# Connectors.net
KiCad netlist of a schematic drawn in Altium Designer
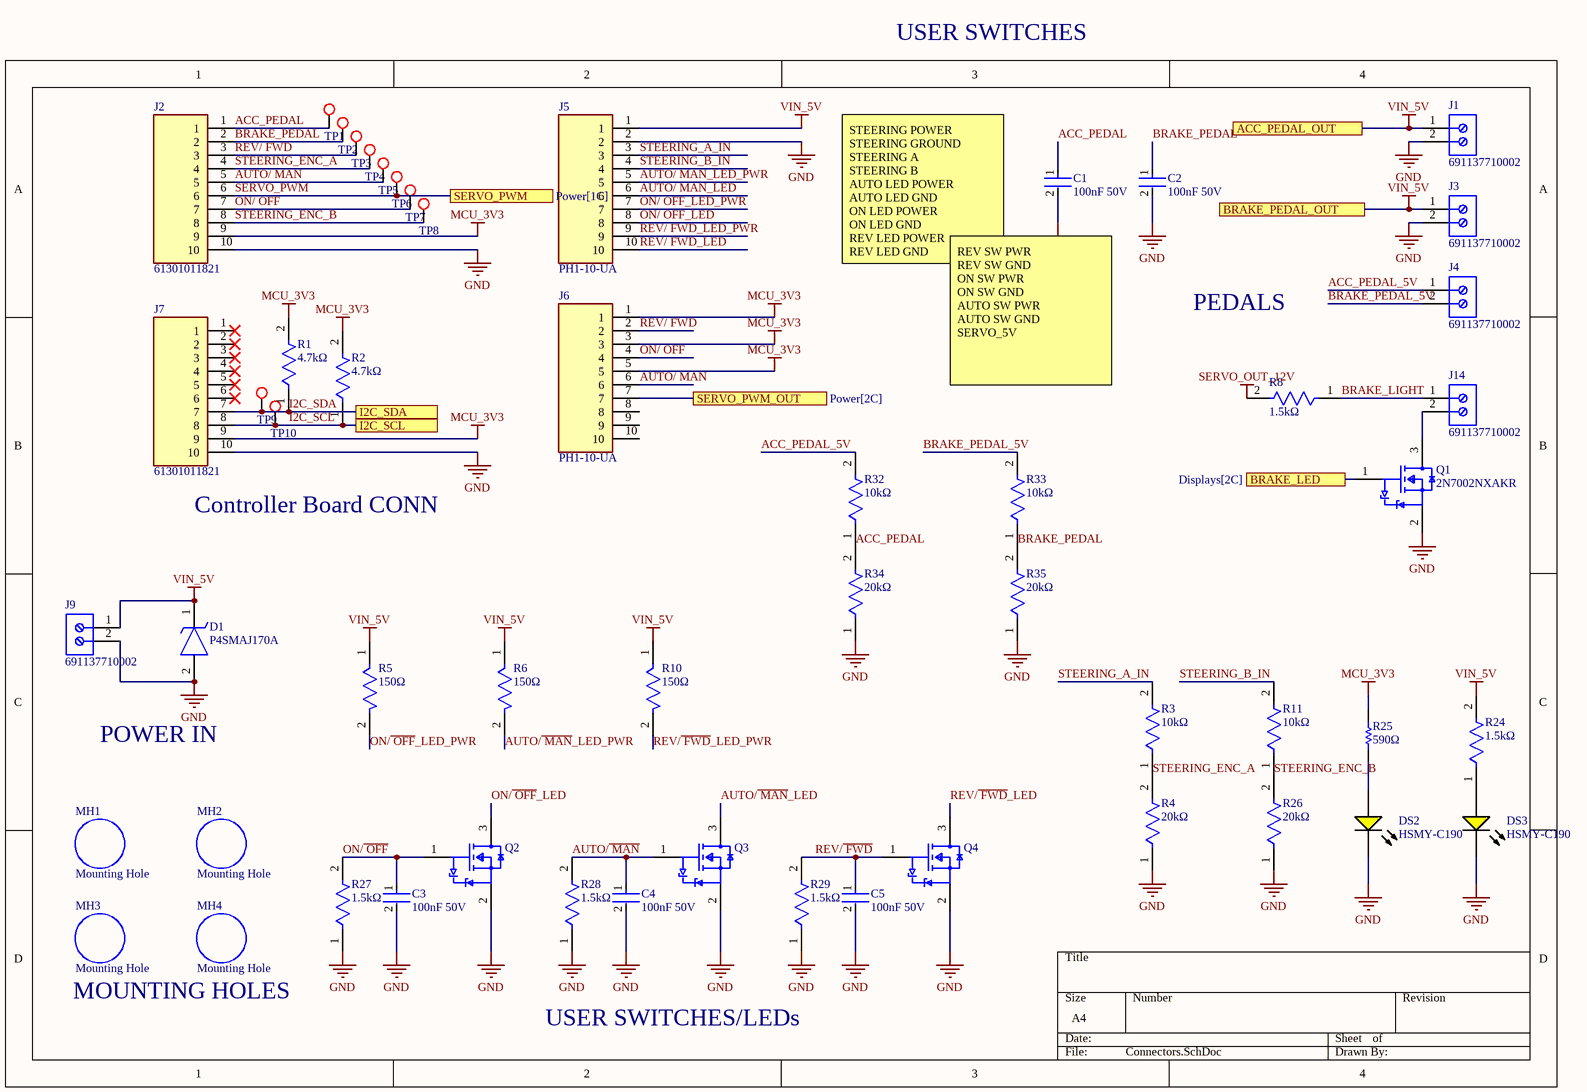
[diagram p0: Connectors.SchDoc]

(export (version "E")
  (design (tool "Eeschema 10.0.6"))
  (components
    (comp (ref "C1")
      (value "100nF 50V")
      (footprint "FP-CL31-IPC_C")
      (description "Cap Ceramic 100nF 50V X7R ±10% SMD 1206 +125°C Embossed T/R")
      (fields (field (name "TOLERANCE") "10%"))
      (libsource (lib "Altium Content Vault") (part "b4654b650e69147ec39a6b967a45e02"))
    )
    (comp (ref "C2")
      (value "100nF 50V")
      (footprint "FP-CL31-IPC_C")
      (description "Cap Ceramic 100nF 50V X7R ±10% SMD 1206 +125°C Embossed T/R")
      (fields (field (name "TOLERANCE") "10%"))
      (libsource (lib "Altium Content Vault") (part "b4654b650e69147ec39a6b967a45e02"))
    )
    (comp (ref "C3")
      (value "100nF 50V")
      (footprint "FP-CL31-IPC_C")
      (description "Cap Ceramic 100nF 50V X7R ±10% SMD 1206 +125°C Embossed T/R")
      (fields (field (name "TOLERANCE") "10%"))
      (libsource (lib "Altium Content Vault") (part "b4654b650e69147ec39a6b967a45e02"))
    )
    (comp (ref "C4")
      (value "100nF 50V")
      (footprint "FP-CL31-IPC_C")
      (description "Cap Ceramic 100nF 50V X7R ±10% SMD 1206 +125°C Embossed T/R")
      (fields (field (name "TOLERANCE") "10%"))
      (libsource (lib "Altium Content Vault") (part "b4654b650e69147ec39a6b967a45e02"))
    )
    (comp (ref "C5")
      (value "100nF 50V")
      (footprint "FP-CL31-IPC_C")
      (description "Cap Ceramic 100nF 50V X7R ±10% SMD 1206 +125°C Embossed T/R")
      (fields (field (name "TOLERANCE") "10%"))
      (libsource (lib "Altium Content Vault") (part "b4654b650e69147ec39a6b967a45e02"))
    )
    (comp (ref "D1")
      (value "P4SMAJ170A")
      (footprint "SamacSys:DIOM5027X240N")
      (description "TVS Diode (Uni-directional)")
      (libsource (lib "*") (part "P4SMAJ170A"))
    )
    (comp (ref "DS2")
      (value "HSMY-C190")
      (footprint "AVAG-HSMX-C190_V")
      (description "LED Uni-Color Yellow, 65 mW, 20 mA, -40 to 85 degC, 2-Pin SMD, RoHS, Tape and Reel")
      (fields (field (name "TOLERANCE") "1%"))
      (libsource (lib "Altium Content Vault") (part "LED-YELLOW-AK-2"))
    )
    (comp (ref "DS3")
      (value "HSMY-C190")
      (footprint "AVAG-HSMX-C190_V")
      (description "LED Uni-Color Yellow, 65 mW, 20 mA, -40 to 85 degC, 2-Pin SMD, RoHS, Tape and Reel")
      (fields (field (name "TOLERANCE") "1%"))
      (libsource (lib "Altium Content Vault") (part "LED-YELLOW-AK-2"))
    )
    (comp (ref "J1")
      (value "691137710002")
      (footprint "691137710002")
      (libsource (lib "Altium Content Vault") (part "TBL - 1R - 02P - Screw"))
    )
    (comp (ref "J2")
      (value "61301011821")
      (footprint "SamacSys:RHDR10W60P0X254_1X10_2590X250X850P")
      (description "Connector")
      (fields (field (name "MOUSER PART NUMBER") "710-61301011821"))
      (libsource (lib "*") (part "61301011821"))
    )
    (comp (ref "J3")
      (value "691137710002")
      (footprint "691137710002")
      (libsource (lib "Altium Content Vault") (part "TBL - 1R - 02P - Screw"))
    )
    (comp (ref "J4")
      (value "691137710002")
      (footprint "691137710002")
      (libsource (lib "Altium Content Vault") (part "TBL - 1R - 02P - Screw"))
    )
    (comp (ref "J5")
      (value "PH1-10-UA")
      (footprint "SamacSys:HDRV10W64P0X254_1X10_2540X249X886P")
      (description "Connector")
      (fields (field (name "MOUSER PART NUMBER") "737-PH1-10-UA"))
      (libsource (lib "*") (part "PH1-10-UA"))
    )
    (comp (ref "J6")
      (value "PH1-10-UA")
      (footprint "SamacSys:HDRV10W64P0X254_1X10_2540X249X886P")
      (description "Connector")
      (fields (field (name "MOUSER PART NUMBER") "737-PH1-10-UA"))
      (libsource (lib "*") (part "PH1-10-UA"))
    )
    (comp (ref "J7")
      (value "61301011821")
      (footprint "SamacSys:RHDR10W60P0X254_1X10_2590X250X850P")
      (description "Connector")
      (fields (field (name "MOUSER PART NUMBER") "710-61301011821"))
      (libsource (lib "*") (part "61301011821"))
    )
    (comp (ref "J9")
      (value "691137710002")
      (footprint "691137710002")
      (libsource (lib "Altium Content Vault") (part "TBL - 1R - 02P - Screw"))
    )
    (comp (ref "J14")
      (value "691137710002")
      (footprint "691137710002")
      (libsource (lib "Altium Content Vault") (part "TBL - 1R - 02P - Screw"))
    )
    (comp (ref "MH1")
      (value "Mounting Hole")
      (footprint "Mounting Hole")
      (libsource (lib "Schlib1") (part "Mounting Hole"))
    )
    (comp (ref "MH2")
      (value "Mounting Hole")
      (footprint "Mounting Hole")
      (libsource (lib "Schlib1") (part "Mounting Hole"))
    )
    (comp (ref "MH3")
      (value "Mounting Hole")
      (footprint "Mounting Hole")
      (libsource (lib "Schlib1") (part "Mounting Hole"))
    )
    (comp (ref "MH4")
      (value "Mounting Hole")
      (footprint "Mounting Hole")
      (libsource (lib "Schlib1") (part "Mounting Hole"))
    )
    (comp (ref "Q1")
      (value "2N7002NXAKR")
      (footprint "FP-SOT23-IPC_B")
      (description "2N7002NXAK/SOT23/TO-236AB")
      (libsource (lib "Altium Content Vault") (part "bf18956dcdab3ff4da62eb44f668dfe"))
    )
    (comp (ref "Q2")
      (value "2N7002NXAKR")
      (footprint "FP-SOT23-IPC_B")
      (description "2N7002NXAK/SOT23/TO-236AB")
      (libsource (lib "Altium Content Vault") (part "bf18956dcdab3ff4da62eb44f668dfe"))
    )
    (comp (ref "Q3")
      (value "2N7002NXAKR")
      (footprint "FP-SOT23-IPC_B")
      (description "2N7002NXAK/SOT23/TO-236AB")
      (libsource (lib "Altium Content Vault") (part "bf18956dcdab3ff4da62eb44f668dfe"))
    )
    (comp (ref "Q4")
      (value "2N7002NXAKR")
      (footprint "FP-SOT23-IPC_B")
      (description "2N7002NXAK/SOT23/TO-236AB")
      (libsource (lib "Altium Content Vault") (part "bf18956dcdab3ff4da62eb44f668dfe"))
    )
    (comp (ref "R1")
      (value "4.7kΩ")
      (footprint "FP-RT0805-MFG")
      (description "RES SMD 4.7K OHM 1% 1/8W 0805")
      (fields (field (name "TOLERANCE") "0.0001") (field (name "MANUFACTURER PART NUMBER") "RT0805FRE074K7L"))
      (libsource (lib "Altium Content Vault") (part "1029c3af85768c4190bb7ad29bc67b5"))
    )
    (comp (ref "R2")
      (value "4.7kΩ")
      (footprint "FP-RT0805-MFG")
      (description "RES SMD 4.7K OHM 1% 1/8W 0805")
      (fields (field (name "TOLERANCE") "0.0001") (field (name "MANUFACTURER PART NUMBER") "RT0805FRE074K7L"))
      (libsource (lib "Altium Content Vault") (part "1029c3af85768c4190bb7ad29bc67b5"))
    )
    (comp (ref "R3")
      (value "10kΩ")
      (footprint "FP-RT0603-MFG")
      (description "RES SMD 10K OHM 0.1% 1/10W 0603")
      (fields
        (field (name "TOLERANCE") "0.001")
        (field (name "OCTOPART") "https://octopart.com/rt0603bre0710kl-yageo-1273959")
      )
      (libsource (lib "Altium Content Vault") (part "1029c3af85768c4190bb7ad29bc67b5"))
    )
    (comp (ref "R4")
      (value "20kΩ")
      (footprint "FP-RT0805-MFG")
      (description "RES SMD 20K OHM 1% 1/8W 0805")
      (fields
        (field (name "MANUFACTURER") "Yageo")
        (field (name "MANUFACTURER PART NUMBER") "RT0805FRE0720KL")
      )
      (libsource (lib "Altium Content Vault") (part "1029c3af85768c4190bb7ad29bc67b5"))
    )
    (comp (ref "R5")
      (value "150Ω")
      (footprint "FP-RT0603-MFG")
      (description "RES SMD 150 OHM 1% 1/10W 0603")
      (fields
        (field (name "OCTOPART") "https://octopart.com/rt0603fre07150rl-yageo-39804552")
        (field (name "MANUFACTURER PART NUMBER") "RT0603FRE07150RL")
      )
      (libsource (lib "Altium Content Vault") (part "1029c3af85768c4190bb7ad29bc67b5"))
    )
    (comp (ref "R6")
      (value "150Ω")
      (footprint "FP-RT0603-MFG")
      (description "RES SMD 150 OHM 1% 1/10W 0603")
      (fields
        (field (name "OCTOPART") "https://octopart.com/rt0603fre07150rl-yageo-39804552")
        (field (name "MANUFACTURER PART NUMBER") "RT0603FRE07150RL")
      )
      (libsource (lib "Altium Content Vault") (part "1029c3af85768c4190bb7ad29bc67b5"))
    )
    (comp (ref "R8")
      (value "1.5kΩ")
      (footprint "FP-CRCW0603-e3-IPC_A")
      (description "RES Thick Film, 1.5kΩ, 1%, 0.1W, 100ppm/°C, 0603")
      (fields (field (name "TOLERANCE") "1%"))
      (libsource (lib "Altium Content Vault") (part "1029c3af85768c4190bb7ad29bc67b5"))
    )
    (comp (ref "R10")
      (value "150Ω")
      (footprint "FP-RT0603-MFG")
      (description "RES SMD 150 OHM 1% 1/10W 0603")
      (fields
        (field (name "OCTOPART") "https://octopart.com/rt0603fre07150rl-yageo-39804552")
        (field (name "MANUFACTURER PART NUMBER") "RT0603FRE07150RL")
      )
      (libsource (lib "Altium Content Vault") (part "1029c3af85768c4190bb7ad29bc67b5"))
    )
    (comp (ref "R11")
      (value "10kΩ")
      (footprint "FP-RT0603-MFG")
      (description "RES SMD 10K OHM 0.1% 1/10W 0603")
      (fields
        (field (name "TOLERANCE") "0.001")
        (field (name "OCTOPART") "https://octopart.com/rt0603bre0710kl-yageo-1273959")
      )
      (libsource (lib "Altium Content Vault") (part "1029c3af85768c4190bb7ad29bc67b5"))
    )
    (comp (ref "R24")
      (value "1.5kΩ")
      (footprint "FP-RC1608-IPC_B")
      (description "Res Thick Film 0603 1.5kΩ 1% 0.1W ±100ppm/°C Molded SMD T/R")
      (fields (field (name "TOLERANCE") "1%"))
      (libsource (lib "Altium Content Vault") (part "1029c3af85768c4190bb7ad29bc67b5"))
    )
    (comp (ref "R25")
      (value "590Ω")
      (footprint "RESC1608X55X25ML10T15")
      (fields (field (name "PART NUMBER") "RC0603FR-07590RL") (field (name "MANUFACTURER") "Yageo"))
      (libsource (lib "Altium Content Vault") (part "RES"))
    )
    (comp (ref "R26")
      (value "20kΩ")
      (footprint "FP-RT0805-MFG")
      (description "RES SMD 20K OHM 1% 1/8W 0805")
      (fields
        (field (name "MANUFACTURER") "Yageo")
        (field (name "MANUFACTURER PART NUMBER") "RT0805FRE0720KL")
      )
      (libsource (lib "Altium Content Vault") (part "1029c3af85768c4190bb7ad29bc67b5"))
    )
    (comp (ref "R27")
      (value "1.5kΩ")
      (footprint "FP-CRCW0603-e3-IPC_A")
      (description "RES Thick Film, 1.5kΩ, 1%, 0.1W, 100ppm/°C, 0603")
      (fields (field (name "TOLERANCE") "1%"))
      (libsource (lib "Altium Content Vault") (part "1029c3af85768c4190bb7ad29bc67b5"))
    )
    (comp (ref "R28")
      (value "1.5kΩ")
      (footprint "FP-CRCW0603-e3-IPC_A")
      (description "RES Thick Film, 1.5kΩ, 1%, 0.1W, 100ppm/°C, 0603")
      (fields (field (name "TOLERANCE") "1%"))
      (libsource (lib "Altium Content Vault") (part "1029c3af85768c4190bb7ad29bc67b5"))
    )
    (comp (ref "R29")
      (value "1.5kΩ")
      (footprint "FP-CRCW0603-e3-IPC_A")
      (description "RES Thick Film, 1.5kΩ, 1%, 0.1W, 100ppm/°C, 0603")
      (fields (field (name "TOLERANCE") "1%"))
      (libsource (lib "Altium Content Vault") (part "1029c3af85768c4190bb7ad29bc67b5"))
    )
    (comp (ref "R32")
      (value "10kΩ")
      (footprint "FP-RT0603-MFG")
      (description "RES SMD 10K OHM 0.1% 1/10W 0603")
      (fields
        (field (name "TOLERANCE") "0.001")
        (field (name "OCTOPART") "https://octopart.com/rt0603bre0710kl-yageo-1273959")
      )
      (libsource (lib "Altium Content Vault") (part "1029c3af85768c4190bb7ad29bc67b5"))
    )
    (comp (ref "R33")
      (value "10kΩ")
      (footprint "FP-RT0603-MFG")
      (description "RES SMD 10K OHM 0.1% 1/10W 0603")
      (fields
        (field (name "TOLERANCE") "0.001")
        (field (name "OCTOPART") "https://octopart.com/rt0603bre0710kl-yageo-1273959")
      )
      (libsource (lib "Altium Content Vault") (part "1029c3af85768c4190bb7ad29bc67b5"))
    )
    (comp (ref "R34")
      (value "20kΩ")
      (footprint "FP-RT0805-MFG")
      (description "RES SMD 20K OHM 1% 1/8W 0805")
      (fields
        (field (name "MANUFACTURER") "Yageo")
        (field (name "MANUFACTURER PART NUMBER") "RT0805FRE0720KL")
      )
      (libsource (lib "Altium Content Vault") (part "1029c3af85768c4190bb7ad29bc67b5"))
    )
    (comp (ref "R35")
      (value "20kΩ")
      (footprint "FP-RT0805-MFG")
      (description "RES SMD 20K OHM 1% 1/8W 0805")
      (fields
        (field (name "MANUFACTURER") "Yageo")
        (field (name "MANUFACTURER PART NUMBER") "RT0805FRE0720KL")
      )
      (libsource (lib "Altium Content Vault") (part "1029c3af85768c4190bb7ad29bc67b5"))
    )
    (comp (ref "TP1") (value "TP") (footprint "Testpoint") (libsource (lib "Schlib1") (part "Testpoint")))
    (comp (ref "TP2") (value "TP") (footprint "Testpoint") (libsource (lib "Schlib1") (part "Testpoint")))
    (comp (ref "TP3") (value "TP") (footprint "Testpoint") (libsource (lib "Schlib1") (part "Testpoint")))
    (comp (ref "TP4") (value "TP") (footprint "Testpoint") (libsource (lib "Schlib1") (part "Testpoint")))
    (comp (ref "TP5") (value "TP") (footprint "Testpoint") (libsource (lib "Schlib1") (part "Testpoint")))
    (comp (ref "TP6") (value "TP") (footprint "Testpoint") (libsource (lib "Schlib1") (part "Testpoint")))
    (comp (ref "TP7") (value "TP") (footprint "Testpoint") (libsource (lib "Schlib1") (part "Testpoint")))
    (comp (ref "TP8") (value "TP") (footprint "Testpoint") (libsource (lib "Schlib1") (part "Testpoint")))
    (comp (ref "TP9") (value "TP") (footprint "Testpoint") (libsource (lib "Schlib1") (part "Testpoint")))
    (comp (ref "TP10") (value "TP") (footprint "Testpoint") (libsource (lib "Schlib1") (part "Testpoint")))
  )
  (nets
    (net (code "1") (name "/ACC_PEDAL") (class "Default")
      (node (ref "C1") (pin "1") (pinfunction "1_1") (pintype "passive"))
      (node (ref "J2") (pin "1") (pinfunction "1_1") (pintype "passive"))
      (node (ref "R32") (pin "1") (pinfunction "1_1") (pintype "passive"))
      (node (ref "R34") (pin "2") (pinfunction "2_2") (pintype "passive"))
      (node (ref "TP1") (pin "0") (pinfunction "0_0") (pintype "passive"))
    )
    (net (code "2") (name "/ACC_PEDAL_5V") (class "Default")
      (node (ref "J4") (pin "1") (pinfunction "1_1") (pintype "passive"))
      (node (ref "R32") (pin "2") (pinfunction "2_2") (pintype "passive"))
    )
    (net (code "3") (name "/AUTO{slash}~{ MAN}") (class "Default")
      (node (ref "C4") (pin "1") (pinfunction "1_1") (pintype "passive"))
      (node (ref "J2") (pin "5") (pinfunction "5_5") (pintype "passive"))
      (node (ref "J6") (pin "6") (pinfunction "6_6") (pintype "passive"))
      (node (ref "Q3") (pin "1") (pinfunction "G_1") (pintype "passive"))
      (node (ref "R28") (pin "2") (pinfunction "2_2") (pintype "passive"))
      (node (ref "TP5") (pin "0") (pinfunction "0_0") (pintype "passive"))
    )
    (net (code "4") (name "/AUTO{slash}~{ MAN}_LED") (class "Default")
      (node (ref "J5") (pin "6") (pinfunction "6_6") (pintype "passive"))
      (node (ref "Q3") (pin "3") (pinfunction "D_3") (pintype "passive"))
    )
    (net (code "5") (name "/AUTO{slash}~{ MAN}_LED_PWR") (class "Default")
      (node (ref "J5") (pin "5") (pinfunction "5_5") (pintype "passive"))
      (node (ref "R6") (pin "2") (pinfunction "2_2") (pintype "passive"))
    )
    (net (code "6") (name "/BRAKE_LED") (class "Default")
      (node (ref "Q1") (pin "1") (pinfunction "G_1") (pintype "passive"))
    )
    (net (code "7") (name "/BRAKE_LIGHT") (class "Default")
      (node (ref "J14") (pin "1") (pinfunction "1_1") (pintype "passive"))
      (node (ref "R8") (pin "1") (pinfunction "1_1") (pintype "passive"))
    )
    (net (code "8") (name "/BRAKE_PEDAL") (class "Default")
      (node (ref "C2") (pin "1") (pinfunction "1_1") (pintype "passive"))
      (node (ref "J2") (pin "2") (pinfunction "2_2") (pintype "passive"))
      (node (ref "R33") (pin "1") (pinfunction "1_1") (pintype "passive"))
      (node (ref "R35") (pin "2") (pinfunction "2_2") (pintype "passive"))
      (node (ref "TP2") (pin "0") (pinfunction "0_0") (pintype "passive"))
    )
    (net (code "9") (name "/BRAKE_PEDAL_5V") (class "Default")
      (node (ref "J4") (pin "2") (pinfunction "2_2") (pintype "passive"))
      (node (ref "R33") (pin "2") (pinfunction "2_2") (pintype "passive"))
    )
    (net (code "10") (name "/I2C_SCL") (class "Default")
      (node (ref "J7") (pin "8") (pinfunction "8_8") (pintype "passive"))
      (node (ref "R2") (pin "1") (pinfunction "1_1") (pintype "passive"))
      (node (ref "TP10") (pin "0") (pinfunction "0_0") (pintype "passive"))
    )
    (net (code "11") (name "/I2C_SDA") (class "Default")
      (node (ref "J7") (pin "7") (pinfunction "7_7") (pintype "passive"))
      (node (ref "R1") (pin "1") (pinfunction "1_1") (pintype "passive"))
      (node (ref "TP9") (pin "0") (pinfunction "0_0") (pintype "passive"))
    )
    (net (code "12") (name "/ON{slash}~{ OFF}") (class "Default")
      (node (ref "C3") (pin "1") (pinfunction "1_1") (pintype "passive"))
      (node (ref "J2") (pin "7") (pinfunction "7_7") (pintype "passive"))
      (node (ref "J6") (pin "4") (pinfunction "4_4") (pintype "passive"))
      (node (ref "Q2") (pin "1") (pinfunction "G_1") (pintype "passive"))
      (node (ref "R27") (pin "2") (pinfunction "2_2") (pintype "passive"))
      (node (ref "TP7") (pin "0") (pinfunction "0_0") (pintype "passive"))
    )
    (net (code "13") (name "/ON{slash}~{ OFF}_LED") (class "Default")
      (node (ref "J5") (pin "8") (pinfunction "8_8") (pintype "passive"))
      (node (ref "Q2") (pin "3") (pinfunction "D_3") (pintype "passive"))
    )
    (net (code "14") (name "/ON{slash}~{ OFF}_LED_PWR") (class "Default")
      (node (ref "J5") (pin "7") (pinfunction "7_7") (pintype "passive"))
      (node (ref "R5") (pin "2") (pinfunction "2_2") (pintype "passive"))
    )
    (net (code "15") (name "/REV{slash}~{ FWD}") (class "Default")
      (node (ref "C5") (pin "1") (pinfunction "1_1") (pintype "passive"))
      (node (ref "J2") (pin "3") (pinfunction "3_3") (pintype "passive"))
      (node (ref "J6") (pin "2") (pinfunction "2_2") (pintype "passive"))
      (node (ref "Q4") (pin "1") (pinfunction "G_1") (pintype "passive"))
      (node (ref "R29") (pin "2") (pinfunction "2_2") (pintype "passive"))
      (node (ref "TP3") (pin "0") (pinfunction "0_0") (pintype "passive"))
    )
    (net (code "16") (name "/REV{slash}~{ FWD}_LED") (class "Default")
      (node (ref "J5") (pin "10") (pinfunction "10_10") (pintype "passive"))
      (node (ref "Q4") (pin "3") (pinfunction "D_3") (pintype "passive"))
    )
    (net (code "17") (name "/REV{slash}~{ FWD}_LED_PWR") (class "Default")
      (node (ref "J5") (pin "9") (pinfunction "9_9") (pintype "passive"))
      (node (ref "R10") (pin "2") (pinfunction "2_2") (pintype "passive"))
    )
    (net (code "18") (name "/SERVO_PWM") (class "Default")
      (node (ref "J2") (pin "6") (pinfunction "6_6") (pintype "passive"))
      (node (ref "TP6") (pin "0") (pinfunction "0_0") (pintype "passive"))
    )
    (net (code "19") (name "/SERVO_PWM_OUT") (class "Default")
      (node (ref "J6") (pin "7") (pinfunction "7_7") (pintype "passive"))
    )
    (net (code "20") (name "/STEERING_A_IN") (class "Default")
      (node (ref "J5") (pin "3") (pinfunction "3_3") (pintype "passive"))
      (node (ref "R3") (pin "2") (pinfunction "2_2") (pintype "passive"))
    )
    (net (code "21") (name "/STEERING_B_IN") (class "Default")
      (node (ref "J5") (pin "4") (pinfunction "4_4") (pintype "passive"))
      (node (ref "R11") (pin "2") (pinfunction "2_2") (pintype "passive"))
    )
    (net (code "22") (name "/STEERING_ENC_A") (class "Default")
      (node (ref "J2") (pin "4") (pinfunction "4_4") (pintype "passive"))
      (node (ref "R3") (pin "1") (pinfunction "1_1") (pintype "passive"))
      (node (ref "R4") (pin "2") (pinfunction "2_2") (pintype "passive"))
      (node (ref "TP4") (pin "0") (pinfunction "0_0") (pintype "passive"))
    )
    (net (code "23") (name "/STEERING_ENC_B") (class "Default")
      (node (ref "J2") (pin "8") (pinfunction "8_8") (pintype "passive"))
      (node (ref "R11") (pin "1") (pinfunction "1_1") (pintype "passive"))
      (node (ref "R26") (pin "2") (pinfunction "2_2") (pintype "passive"))
      (node (ref "TP8") (pin "0") (pinfunction "0_0") (pintype "passive"))
    )
    (net (code "24") (name "GND") (class "Default")
      (node (ref "C1") (pin "2") (pinfunction "2_2") (pintype "passive"))
      (node (ref "C2") (pin "2") (pinfunction "2_2") (pintype "passive"))
      (node (ref "C3") (pin "2") (pinfunction "2_2") (pintype "passive"))
      (node (ref "C4") (pin "2") (pinfunction "2_2") (pintype "passive"))
      (node (ref "C5") (pin "2") (pinfunction "2_2") (pintype "passive"))
      (node (ref "D1") (pin "2") (pinfunction "A_2") (pintype "passive"))
      (node (ref "DS2") (pin "2") (pinfunction "K_2") (pintype "passive"))
      (node (ref "DS3") (pin "2") (pinfunction "K_2") (pintype "passive"))
      (node (ref "J1") (pin "2") (pinfunction "2_2") (pintype "passive"))
      (node (ref "J2") (pin "10") (pinfunction "10_10") (pintype "passive"))
      (node (ref "J3") (pin "2") (pinfunction "2_2") (pintype "passive"))
      (node (ref "J5") (pin "2") (pinfunction "2_2") (pintype "passive"))
      (node (ref "J7") (pin "10") (pinfunction "10_10") (pintype "passive"))
      (node (ref "J9") (pin "2") (pinfunction "2_2") (pintype "passive"))
      (node (ref "Q1") (pin "2") (pinfunction "S_2") (pintype "passive"))
      (node (ref "Q2") (pin "2") (pinfunction "S_2") (pintype "passive"))
      (node (ref "Q3") (pin "2") (pinfunction "S_2") (pintype "passive"))
      (node (ref "Q4") (pin "2") (pinfunction "S_2") (pintype "passive"))
      (node (ref "R26") (pin "1") (pinfunction "1_1") (pintype "passive"))
      (node (ref "R27") (pin "1") (pinfunction "1_1") (pintype "passive"))
      (node (ref "R28") (pin "1") (pinfunction "1_1") (pintype "passive"))
      (node (ref "R29") (pin "1") (pinfunction "1_1") (pintype "passive"))
      (node (ref "R34") (pin "1") (pinfunction "1_1") (pintype "passive"))
      (node (ref "R35") (pin "1") (pinfunction "1_1") (pintype "passive"))
      (node (ref "R4") (pin "1") (pinfunction "1_1") (pintype "passive"))
    )
    (net (code "25") (name "MCU_3V3") (class "Default")
      (node (ref "J2") (pin "9") (pinfunction "9_9") (pintype "passive"))
      (node (ref "J6") (pin "1") (pinfunction "1_1") (pintype "passive"))
      (node (ref "J6") (pin "3") (pinfunction "3_3") (pintype "passive"))
      (node (ref "J6") (pin "5") (pinfunction "5_5") (pintype "passive"))
      (node (ref "J7") (pin "9") (pinfunction "9_9") (pintype "passive"))
      (node (ref "R1") (pin "2") (pinfunction "2_2") (pintype "passive"))
      (node (ref "R2") (pin "2") (pinfunction "2_2") (pintype "passive"))
      (node (ref "R25") (pin "2") (pinfunction "2_2") (pintype "passive"))
    )
    (net (code "26") (name "Net-(DS2-A)") (class "Default")
      (node (ref "DS2") (pin "1") (pinfunction "A_1") (pintype "passive"))
      (node (ref "R25") (pin "1") (pinfunction "1_1") (pintype "passive"))
    )
    (net (code "27") (name "Net-(DS3-A)") (class "Default")
      (node (ref "DS3") (pin "1") (pinfunction "A_1") (pintype "passive"))
      (node (ref "R24") (pin "1") (pinfunction "1_1") (pintype "passive"))
    )
    (net (code "28") (name "Net-(Q1-D)") (class "Default")
      (node (ref "J14") (pin "2") (pinfunction "2_2") (pintype "passive"))
      (node (ref "Q1") (pin "3") (pinfunction "D_3") (pintype "passive"))
    )
    (net (code "29") (name "SERVO_OUT_12V") (class "Default")
      (node (ref "R8") (pin "2") (pinfunction "2_2") (pintype "passive"))
    )
    (net (code "30") (name "VIN_5V") (class "Default")
      (node (ref "D1") (pin "1") (pinfunction "K_1") (pintype "passive"))
      (node (ref "J1") (pin "1") (pinfunction "1_1") (pintype "passive"))
      (node (ref "J3") (pin "1") (pinfunction "1_1") (pintype "passive"))
      (node (ref "J5") (pin "1") (pinfunction "1_1") (pintype "passive"))
      (node (ref "J9") (pin "1") (pinfunction "1_1") (pintype "passive"))
      (node (ref "R10") (pin "1") (pinfunction "1_1") (pintype "passive"))
      (node (ref "R24") (pin "2") (pinfunction "2_2") (pintype "passive"))
      (node (ref "R5") (pin "1") (pinfunction "1_1") (pintype "passive"))
      (node (ref "R6") (pin "1") (pinfunction "1_1") (pintype "passive"))
    )
    (net (code "31") (name "unconnected-(J6-Pad8)") (class "Default")
      (node (ref "J6") (pin "8") (pinfunction "8_8") (pintype "passive"))
    )
    (net (code "32") (name "unconnected-(J6-Pad9)") (class "Default")
      (node (ref "J6") (pin "9") (pinfunction "9_9") (pintype "passive"))
    )
    (net (code "33") (name "unconnected-(J6-Pad10)") (class "Default")
      (node (ref "J6") (pin "10") (pinfunction "10_10") (pintype "passive"))
    )
    (net (code "34") (name "unconnected-(J7-Pad1)") (class "Default")
      (node (ref "J7") (pin "1") (pinfunction "1_1") (pintype "passive+no_connect"))
    )
    (net (code "35") (name "unconnected-(J7-Pad2)") (class "Default")
      (node (ref "J7") (pin "2") (pinfunction "2_2") (pintype "passive+no_connect"))
    )
    (net (code "36") (name "unconnected-(J7-Pad3)") (class "Default")
      (node (ref "J7") (pin "3") (pinfunction "3_3") (pintype "passive+no_connect"))
    )
    (net (code "37") (name "unconnected-(J7-Pad4)") (class "Default")
      (node (ref "J7") (pin "4") (pinfunction "4_4") (pintype "passive+no_connect"))
    )
    (net (code "38") (name "unconnected-(J7-Pad5)") (class "Default")
      (node (ref "J7") (pin "5") (pinfunction "5_5") (pintype "passive+no_connect"))
    )
    (net (code "39") (name "unconnected-(J7-Pad6)") (class "Default")
      (node (ref "J7") (pin "6") (pinfunction "6_6") (pintype "passive+no_connect"))
    )
  )
)
